# MuffsyRelayInput2.net
KiCad netlist of a schematic drawn in EAGLE
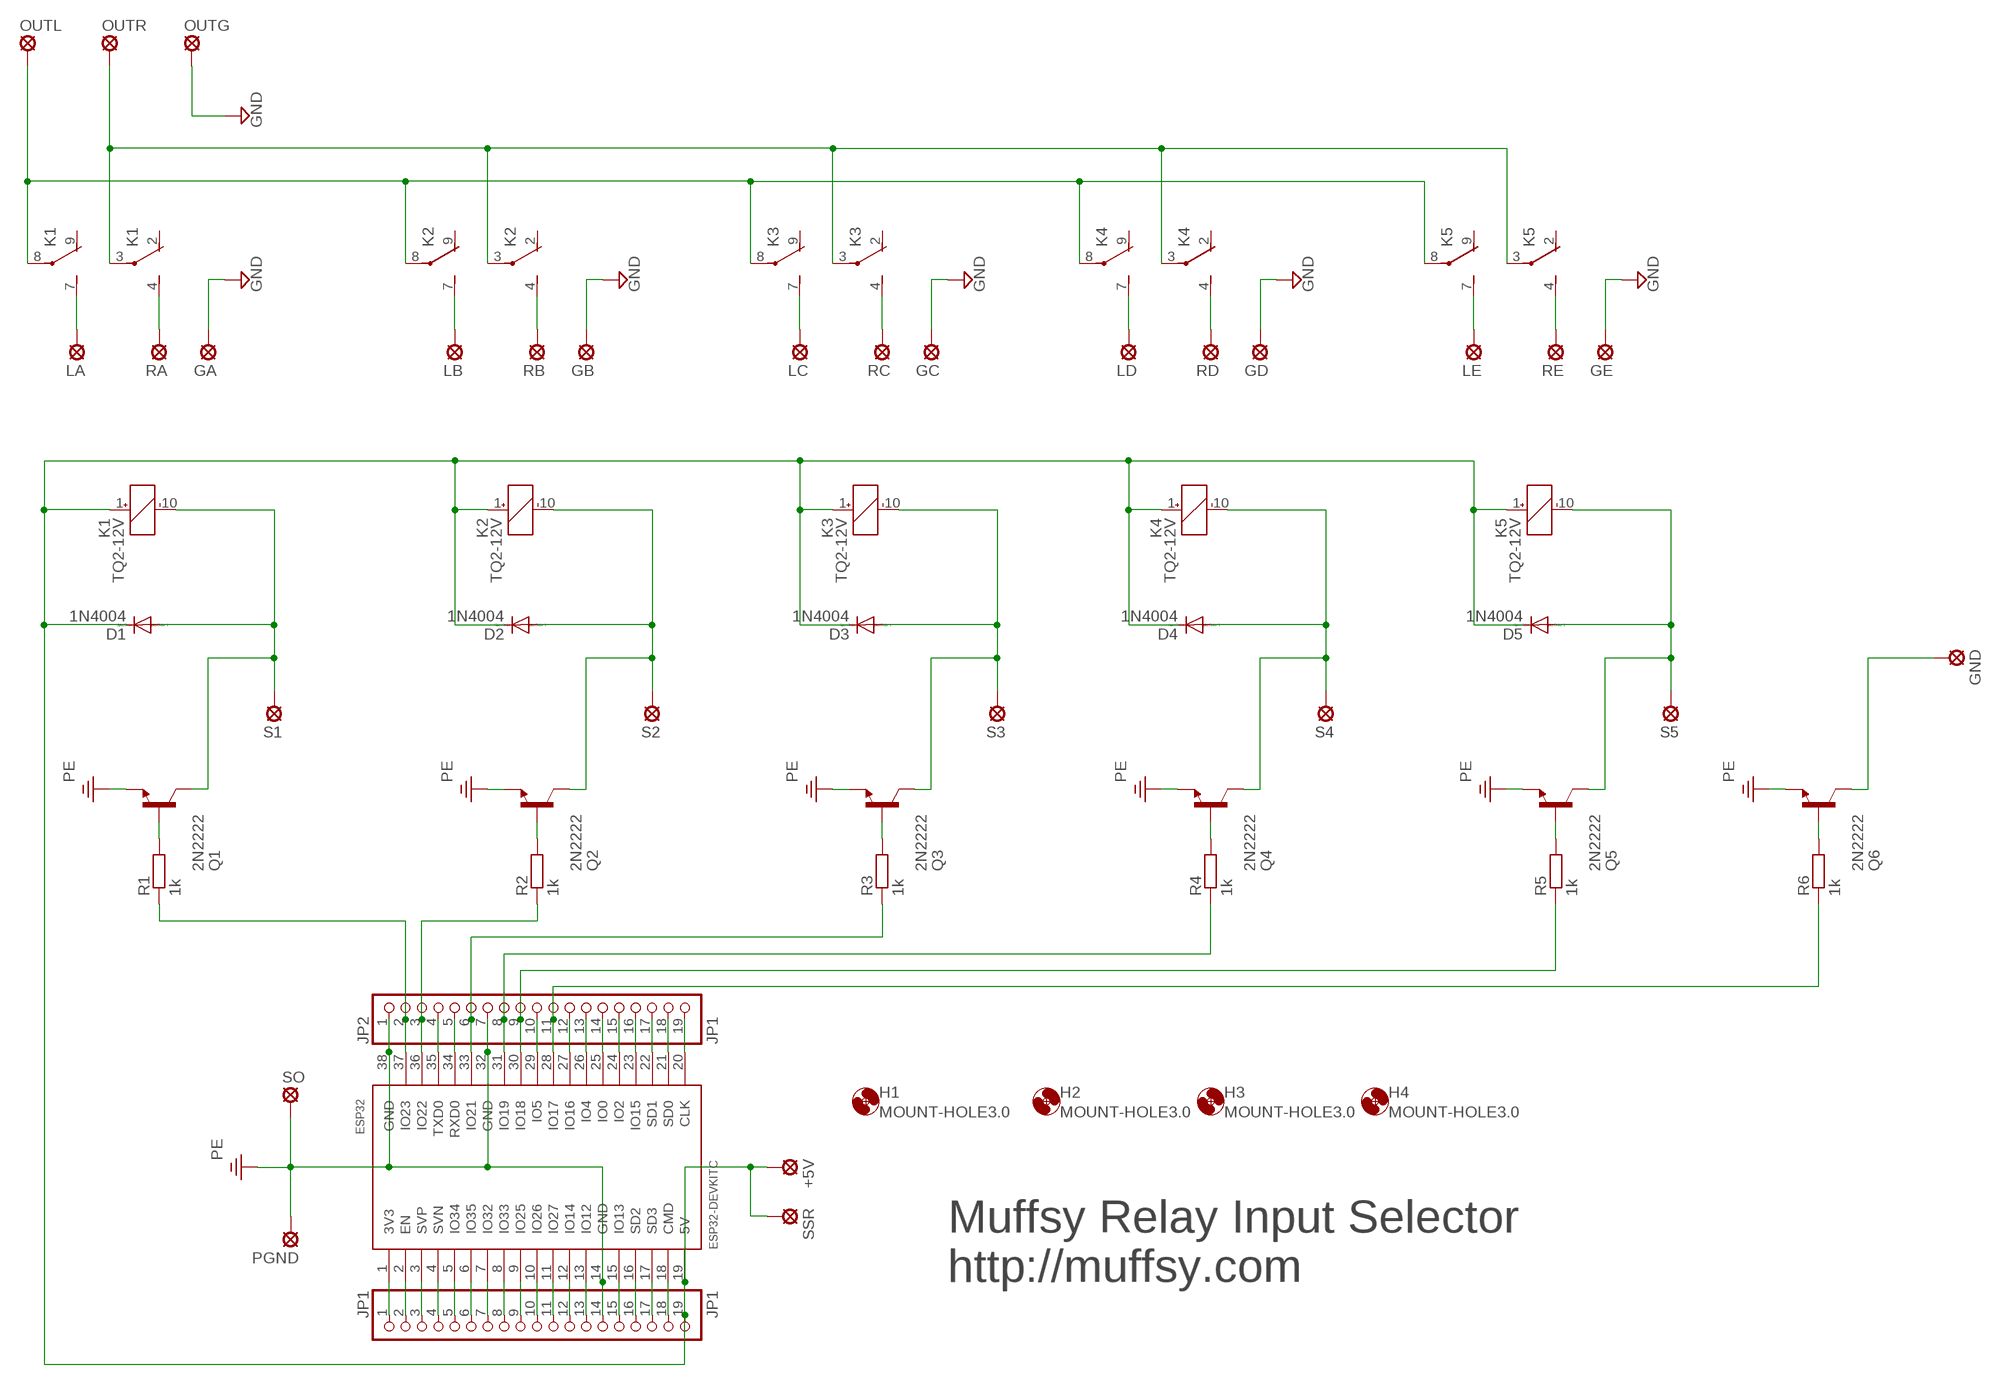
[diagram p0: schematic, sheet 1]

(export (version "E")
  (design (tool "Eeschema 10.0.6"))
  (components
    (comp (ref "+5V")
      (value "SE11")
      (footprint "eagle-import:SE11")
      (libsource (lib "eagle-import") (part "SE11"))
    )
    (comp (ref "D1")
      (value "1N4004")
      (footprint "eagle-import:DO41-10")
      (libsource (lib "eagle-import") (part "1N4004"))
    )
    (comp (ref "D2")
      (value "1N4004")
      (footprint "eagle-import:DO41-10")
      (libsource (lib "eagle-import") (part "1N4004"))
    )
    (comp (ref "D3")
      (value "1N4004")
      (footprint "eagle-import:DO41-10")
      (libsource (lib "eagle-import") (part "1N4004"))
    )
    (comp (ref "D4")
      (value "1N4004")
      (footprint "eagle-import:DO41-10")
      (libsource (lib "eagle-import") (part "1N4004"))
    )
    (comp (ref "D5")
      (value "1N4004")
      (footprint "eagle-import:DO41-10")
      (libsource (lib "eagle-import") (part "1N4004"))
    )
    (comp (ref "ESP32")
      (value "ESP32DEVKITC")
      (footprint "eagle-import:ESP32-DEVKITC")
      (libsource (lib "eagle-import") (part "ESP32DEVKITC"))
    )
    (comp (ref "GA")
      (value "SE11")
      (footprint "eagle-import:SE11")
      (libsource (lib "eagle-import") (part "SE11"))
    )
    (comp (ref "GB")
      (value "SE11")
      (footprint "eagle-import:SE11")
      (libsource (lib "eagle-import") (part "SE11"))
    )
    (comp (ref "GC")
      (value "SE11")
      (footprint "eagle-import:SE11")
      (libsource (lib "eagle-import") (part "SE11"))
    )
    (comp (ref "GD")
      (value "SE11")
      (footprint "eagle-import:SE11")
      (libsource (lib "eagle-import") (part "SE11"))
    )
    (comp (ref "GE")
      (value "SE11")
      (footprint "eagle-import:SE11")
      (libsource (lib "eagle-import") (part "SE11"))
    )
    (comp (ref "GND")
      (value "SE11")
      (footprint "eagle-import:SE11")
      (libsource (lib "eagle-import") (part "SE11"))
    )
    (comp (ref "H1")
      (value "MOUNT-HOLE3.0")
      (footprint "eagle-import:3,0")
      (libsource (lib "eagle-import") (part "MOUNT-HOLE3.0"))
    )
    (comp (ref "H2")
      (value "MOUNT-HOLE3.0")
      (footprint "eagle-import:3,0")
      (libsource (lib "eagle-import") (part "MOUNT-HOLE3.0"))
    )
    (comp (ref "H3")
      (value "MOUNT-HOLE3.0")
      (footprint "eagle-import:3,0")
      (libsource (lib "eagle-import") (part "MOUNT-HOLE3.0"))
    )
    (comp (ref "H4")
      (value "MOUNT-HOLE3.0")
      (footprint "eagle-import:3,0")
      (libsource (lib "eagle-import") (part "MOUNT-HOLE3.0"))
    )
    (comp (ref "JP1")
      (value "JP1")
      (footprint "eagle-import:1X19")
      (libsource (lib "eagle-import") (part "PINHD-1X19"))
    )
    (comp (ref "JP2")
      (value "JP1")
      (footprint "eagle-import:1X19")
      (libsource (lib "eagle-import") (part "PINHD-1X19"))
    )
    (comp (ref "K1")
      (value "TQ2-12V")
      (footprint "eagle-import:TQ2")
      (fields (field (name "MF") "AROMAT/ MATSUSHITA"))
      (libsource (lib "eagle-import") (part "TQ2?-12V"))
    )
    (comp (ref "K2")
      (value "TQ2-12V")
      (footprint "eagle-import:TQ2")
      (fields (field (name "MF") "AROMAT/ MATSUSHITA"))
      (libsource (lib "eagle-import") (part "TQ2?-12V"))
    )
    (comp (ref "K3")
      (value "TQ2-12V")
      (footprint "eagle-import:TQ2")
      (fields (field (name "MF") "AROMAT/ MATSUSHITA"))
      (libsource (lib "eagle-import") (part "TQ2?-12V"))
    )
    (comp (ref "K4")
      (value "TQ2-12V")
      (footprint "eagle-import:TQ2")
      (fields (field (name "MF") "AROMAT/ MATSUSHITA"))
      (libsource (lib "eagle-import") (part "TQ2?-12V"))
    )
    (comp (ref "K5")
      (value "TQ2-12V")
      (footprint "eagle-import:TQ2")
      (fields (field (name "MF") "AROMAT/ MATSUSHITA"))
      (libsource (lib "eagle-import") (part "TQ2?-12V"))
    )
    (comp (ref "LA")
      (value "SE11")
      (footprint "eagle-import:SE11")
      (libsource (lib "eagle-import") (part "SE11"))
    )
    (comp (ref "LB")
      (value "SE11")
      (footprint "eagle-import:SE11")
      (libsource (lib "eagle-import") (part "SE11"))
    )
    (comp (ref "LC")
      (value "SE11")
      (footprint "eagle-import:SE11")
      (libsource (lib "eagle-import") (part "SE11"))
    )
    (comp (ref "LD")
      (value "SE11")
      (footprint "eagle-import:SE11")
      (libsource (lib "eagle-import") (part "SE11"))
    )
    (comp (ref "LE")
      (value "SE11")
      (footprint "eagle-import:SE11")
      (libsource (lib "eagle-import") (part "SE11"))
    )
    (comp (ref "OUTG")
      (value "SE11")
      (footprint "eagle-import:SE11")
      (libsource (lib "eagle-import") (part "SE11"))
    )
    (comp (ref "OUTL")
      (value "SE11")
      (footprint "eagle-import:SE11")
      (libsource (lib "eagle-import") (part "SE11"))
    )
    (comp (ref "OUTR")
      (value "SE11")
      (footprint "eagle-import:SE11")
      (libsource (lib "eagle-import") (part "SE11"))
    )
    (comp (ref "PGND")
      (value "SE11")
      (footprint "eagle-import:SE11")
      (libsource (lib "eagle-import") (part "SE11"))
    )
    (comp (ref "Q1")
      (value "2N2222")
      (footprint "eagle-import:TO18")
      (libsource (lib "eagle-import") (part "2N2222"))
    )
    (comp (ref "Q2")
      (value "2N2222")
      (footprint "eagle-import:TO18")
      (libsource (lib "eagle-import") (part "2N2222"))
    )
    (comp (ref "Q3")
      (value "2N2222")
      (footprint "eagle-import:TO18")
      (libsource (lib "eagle-import") (part "2N2222"))
    )
    (comp (ref "Q4")
      (value "2N2222")
      (footprint "eagle-import:TO18")
      (libsource (lib "eagle-import") (part "2N2222"))
    )
    (comp (ref "Q5")
      (value "2N2222")
      (footprint "eagle-import:TO18")
      (libsource (lib "eagle-import") (part "2N2222"))
    )
    (comp (ref "Q6")
      (value "2N2222")
      (footprint "eagle-import:TO18")
      (libsource (lib "eagle-import") (part "2N2222"))
    )
    (comp (ref "R1")
      (value "1k")
      (footprint "eagle-import:0207_10")
      (libsource (lib "eagle-import") (part "R-EU_0207/10"))
    )
    (comp (ref "R2")
      (value "1k")
      (footprint "eagle-import:0207_10")
      (libsource (lib "eagle-import") (part "R-EU_0207/10"))
    )
    (comp (ref "R3")
      (value "1k")
      (footprint "eagle-import:0207_10")
      (libsource (lib "eagle-import") (part "R-EU_0207/10"))
    )
    (comp (ref "R4")
      (value "1k")
      (footprint "eagle-import:0207_10")
      (libsource (lib "eagle-import") (part "R-EU_0207/10"))
    )
    (comp (ref "R5")
      (value "1k")
      (footprint "eagle-import:0207_10")
      (libsource (lib "eagle-import") (part "R-EU_0207/10"))
    )
    (comp (ref "R6")
      (value "1k")
      (footprint "eagle-import:0207_10")
      (libsource (lib "eagle-import") (part "R-EU_0207/10"))
    )
    (comp (ref "RA")
      (value "SE11")
      (footprint "eagle-import:SE11")
      (libsource (lib "eagle-import") (part "SE11"))
    )
    (comp (ref "RB")
      (value "SE11")
      (footprint "eagle-import:SE11")
      (libsource (lib "eagle-import") (part "SE11"))
    )
    (comp (ref "RC")
      (value "SE11")
      (footprint "eagle-import:SE11")
      (libsource (lib "eagle-import") (part "SE11"))
    )
    (comp (ref "RD")
      (value "SE11")
      (footprint "eagle-import:SE11")
      (libsource (lib "eagle-import") (part "SE11"))
    )
    (comp (ref "RE")
      (value "SE11")
      (footprint "eagle-import:SE11")
      (libsource (lib "eagle-import") (part "SE11"))
    )
    (comp (ref "S1")
      (value "SE11")
      (footprint "eagle-import:SE11")
      (libsource (lib "eagle-import") (part "SE11"))
    )
    (comp (ref "S2")
      (value "SE11")
      (footprint "eagle-import:SE11")
      (libsource (lib "eagle-import") (part "SE11"))
    )
    (comp (ref "S3")
      (value "SE11")
      (footprint "eagle-import:SE11")
      (libsource (lib "eagle-import") (part "SE11"))
    )
    (comp (ref "S4")
      (value "SE11")
      (footprint "eagle-import:SE11")
      (libsource (lib "eagle-import") (part "SE11"))
    )
    (comp (ref "S5")
      (value "SE11")
      (footprint "eagle-import:SE11")
      (libsource (lib "eagle-import") (part "SE11"))
    )
    (comp (ref "SO")
      (value "SE11")
      (footprint "eagle-import:SE11")
      (libsource (lib "eagle-import") (part "SE11"))
    )
    (comp (ref "SSR")
      (value "SE11")
      (footprint "eagle-import:SE11")
      (libsource (lib "eagle-import") (part "SE11"))
    )
  )
  (nets
    (net (code "1") (name "GND") (class "Default")
      (node (ref "GA") (pin "MP") (pinfunction "MP_MP") (pintype "passive"))
      (node (ref "GB") (pin "MP") (pinfunction "MP_MP") (pintype "passive"))
      (node (ref "GC") (pin "MP") (pinfunction "MP_MP") (pintype "passive"))
      (node (ref "GD") (pin "MP") (pinfunction "MP_MP") (pintype "passive"))
      (node (ref "GE") (pin "MP") (pinfunction "MP_MP") (pintype "passive"))
      (node (ref "OUTG") (pin "MP") (pinfunction "MP_MP") (pintype "passive"))
    )
    (net (code "2") (name "Net-(ESP32-3V3)") (class "Default")
      (node (ref "ESP32") (pin "1") (pinfunction "3V3_1") (pintype "bidirectional"))
      (node (ref "JP1") (pin "1") (pinfunction "1_1") (pintype "passive"))
    )
    (net (code "3") (name "Net-(ESP32-5V)") (class "Default")
      (node (ref "+5V") (pin "MP") (pinfunction "MP_MP") (pintype "passive"))
      (node (ref "D1") (pin "C") (pinfunction "C_C") (pintype "passive"))
      (node (ref "D2") (pin "C") (pinfunction "C_C") (pintype "passive"))
      (node (ref "D3") (pin "C") (pinfunction "C_C") (pintype "passive"))
      (node (ref "D4") (pin "C") (pinfunction "C_C") (pintype "passive"))
      (node (ref "D5") (pin "C") (pinfunction "C_C") (pintype "passive"))
      (node (ref "ESP32") (pin "19") (pinfunction "5V_19") (pintype "bidirectional"))
      (node (ref "JP1") (pin "19") (pinfunction "19_19") (pintype "passive"))
      (node (ref "K1") (pin "1") (pinfunction "+_1") (pintype "passive"))
      (node (ref "K2") (pin "1") (pinfunction "+_1") (pintype "passive"))
      (node (ref "K3") (pin "1") (pinfunction "+_1") (pintype "passive"))
      (node (ref "K4") (pin "1") (pinfunction "+_1") (pintype "passive"))
      (node (ref "K5") (pin "1") (pinfunction "+_1") (pintype "passive"))
      (node (ref "SSR") (pin "MP") (pinfunction "MP_MP") (pintype "passive"))
    )
    (net (code "4") (name "Net-(ESP32-CLK)") (class "Default")
      (node (ref "ESP32") (pin "20") (pinfunction "CLK_20") (pintype "bidirectional"))
      (node (ref "JP2") (pin "19") (pinfunction "19_19") (pintype "passive"))
    )
    (net (code "5") (name "Net-(ESP32-CMD)") (class "Default")
      (node (ref "ESP32") (pin "18") (pinfunction "CMD_18") (pintype "bidirectional"))
      (node (ref "JP1") (pin "18") (pinfunction "18_18") (pintype "passive"))
    )
    (net (code "6") (name "Net-(ESP32-EN)") (class "Default")
      (node (ref "ESP32") (pin "2") (pinfunction "EN_2") (pintype "bidirectional"))
      (node (ref "JP1") (pin "2") (pinfunction "2_2") (pintype "passive"))
    )
    (net (code "7") (name "Net-(ESP32-IO0)") (class "Default")
      (node (ref "ESP32") (pin "25") (pinfunction "IO0_25") (pintype "bidirectional"))
      (node (ref "JP2") (pin "14") (pinfunction "14_14") (pintype "passive"))
    )
    (net (code "8") (name "Net-(ESP32-IO2)") (class "Default")
      (node (ref "ESP32") (pin "24") (pinfunction "IO2_24") (pintype "bidirectional"))
      (node (ref "JP2") (pin "15") (pinfunction "15_15") (pintype "passive"))
    )
    (net (code "9") (name "Net-(ESP32-IO4)") (class "Default")
      (node (ref "ESP32") (pin "26") (pinfunction "IO4_26") (pintype "bidirectional"))
      (node (ref "JP2") (pin "13") (pinfunction "13_13") (pintype "passive"))
    )
    (net (code "10") (name "Net-(ESP32-IO5)") (class "Default")
      (node (ref "ESP32") (pin "29") (pinfunction "IO5_29") (pintype "bidirectional"))
      (node (ref "JP2") (pin "10") (pinfunction "10_10") (pintype "passive"))
    )
    (net (code "11") (name "Net-(ESP32-IO12)") (class "Default")
      (node (ref "ESP32") (pin "13") (pinfunction "IO12_13") (pintype "bidirectional"))
      (node (ref "JP1") (pin "13") (pinfunction "13_13") (pintype "passive"))
    )
    (net (code "12") (name "Net-(ESP32-IO13)") (class "Default")
      (node (ref "ESP32") (pin "15") (pinfunction "IO13_15") (pintype "bidirectional"))
      (node (ref "JP1") (pin "15") (pinfunction "15_15") (pintype "passive"))
    )
    (net (code "13") (name "Net-(ESP32-IO14)") (class "Default")
      (node (ref "ESP32") (pin "12") (pinfunction "IO14_12") (pintype "bidirectional"))
      (node (ref "JP1") (pin "12") (pinfunction "12_12") (pintype "passive"))
    )
    (net (code "14") (name "Net-(ESP32-IO15)") (class "Default")
      (node (ref "ESP32") (pin "23") (pinfunction "IO15_23") (pintype "bidirectional"))
      (node (ref "JP2") (pin "16") (pinfunction "16_16") (pintype "passive"))
    )
    (net (code "15") (name "Net-(ESP32-IO16)") (class "Default")
      (node (ref "ESP32") (pin "27") (pinfunction "IO16_27") (pintype "bidirectional"))
      (node (ref "JP2") (pin "12") (pinfunction "12_12") (pintype "passive"))
    )
    (net (code "16") (name "Net-(ESP32-IO17)") (class "Default")
      (node (ref "ESP32") (pin "28") (pinfunction "IO17_28") (pintype "bidirectional"))
      (node (ref "JP2") (pin "11") (pinfunction "11_11") (pintype "passive"))
      (node (ref "R6") (pin "1") (pinfunction "1_1") (pintype "passive"))
    )
    (net (code "17") (name "Net-(ESP32-IO18)") (class "Default")
      (node (ref "ESP32") (pin "30") (pinfunction "IO18_30") (pintype "bidirectional"))
      (node (ref "JP2") (pin "9") (pinfunction "9_9") (pintype "passive"))
      (node (ref "R5") (pin "1") (pinfunction "1_1") (pintype "passive"))
    )
    (net (code "18") (name "Net-(ESP32-IO19)") (class "Default")
      (node (ref "ESP32") (pin "31") (pinfunction "IO19_31") (pintype "bidirectional"))
      (node (ref "JP2") (pin "8") (pinfunction "8_8") (pintype "passive"))
      (node (ref "R4") (pin "1") (pinfunction "1_1") (pintype "passive"))
    )
    (net (code "19") (name "Net-(ESP32-IO21)") (class "Default")
      (node (ref "ESP32") (pin "33") (pinfunction "IO21_33") (pintype "bidirectional"))
      (node (ref "JP2") (pin "6") (pinfunction "6_6") (pintype "passive"))
      (node (ref "R3") (pin "1") (pinfunction "1_1") (pintype "passive"))
    )
    (net (code "20") (name "Net-(ESP32-IO22)") (class "Default")
      (node (ref "ESP32") (pin "36") (pinfunction "IO22_36") (pintype "bidirectional"))
      (node (ref "JP2") (pin "3") (pinfunction "3_3") (pintype "passive"))
      (node (ref "R2") (pin "1") (pinfunction "1_1") (pintype "passive"))
    )
    (net (code "21") (name "Net-(ESP32-IO23)") (class "Default")
      (node (ref "ESP32") (pin "37") (pinfunction "IO23_37") (pintype "bidirectional"))
      (node (ref "JP2") (pin "2") (pinfunction "2_2") (pintype "passive"))
      (node (ref "R1") (pin "1") (pinfunction "1_1") (pintype "passive"))
    )
    (net (code "22") (name "Net-(ESP32-IO25)") (class "Default")
      (node (ref "ESP32") (pin "9") (pinfunction "IO25_9") (pintype "bidirectional"))
      (node (ref "JP1") (pin "9") (pinfunction "9_9") (pintype "passive"))
    )
    (net (code "23") (name "Net-(ESP32-IO26)") (class "Default")
      (node (ref "ESP32") (pin "10") (pinfunction "IO26_10") (pintype "bidirectional"))
      (node (ref "JP1") (pin "10") (pinfunction "10_10") (pintype "passive"))
    )
    (net (code "24") (name "Net-(ESP32-IO27)") (class "Default")
      (node (ref "ESP32") (pin "11") (pinfunction "IO27_11") (pintype "bidirectional"))
      (node (ref "JP1") (pin "11") (pinfunction "11_11") (pintype "passive"))
    )
    (net (code "25") (name "Net-(ESP32-IO32)") (class "Default")
      (node (ref "ESP32") (pin "7") (pinfunction "IO32_7") (pintype "bidirectional"))
      (node (ref "JP1") (pin "7") (pinfunction "7_7") (pintype "passive"))
    )
    (net (code "26") (name "Net-(ESP32-IO33)") (class "Default")
      (node (ref "ESP32") (pin "8") (pinfunction "IO33_8") (pintype "bidirectional"))
      (node (ref "JP1") (pin "8") (pinfunction "8_8") (pintype "passive"))
    )
    (net (code "27") (name "Net-(ESP32-IO34)") (class "Default")
      (node (ref "ESP32") (pin "5") (pinfunction "IO34_5") (pintype "bidirectional"))
      (node (ref "JP1") (pin "5") (pinfunction "5_5") (pintype "passive"))
    )
    (net (code "28") (name "Net-(ESP32-IO35)") (class "Default")
      (node (ref "ESP32") (pin "6") (pinfunction "IO35_6") (pintype "bidirectional"))
      (node (ref "JP1") (pin "6") (pinfunction "6_6") (pintype "passive"))
    )
    (net (code "29") (name "Net-(ESP32-RXD0)") (class "Default")
      (node (ref "ESP32") (pin "34") (pinfunction "RXD0_34") (pintype "bidirectional"))
      (node (ref "JP2") (pin "5") (pinfunction "5_5") (pintype "passive"))
    )
    (net (code "30") (name "Net-(ESP32-SD0)") (class "Default")
      (node (ref "ESP32") (pin "21") (pinfunction "SD0_21") (pintype "bidirectional"))
      (node (ref "JP2") (pin "18") (pinfunction "18_18") (pintype "passive"))
    )
    (net (code "31") (name "Net-(ESP32-SD1)") (class "Default")
      (node (ref "ESP32") (pin "22") (pinfunction "SD1_22") (pintype "bidirectional"))
      (node (ref "JP2") (pin "17") (pinfunction "17_17") (pintype "passive"))
    )
    (net (code "32") (name "Net-(ESP32-SD2)") (class "Default")
      (node (ref "ESP32") (pin "16") (pinfunction "SD2_16") (pintype "bidirectional"))
      (node (ref "JP1") (pin "16") (pinfunction "16_16") (pintype "passive"))
    )
    (net (code "33") (name "Net-(ESP32-SD3)") (class "Default")
      (node (ref "ESP32") (pin "17") (pinfunction "SD3_17") (pintype "bidirectional"))
      (node (ref "JP1") (pin "17") (pinfunction "17_17") (pintype "passive"))
    )
    (net (code "34") (name "Net-(ESP32-SVN)") (class "Default")
      (node (ref "ESP32") (pin "4") (pinfunction "SVN_4") (pintype "bidirectional"))
      (node (ref "JP1") (pin "4") (pinfunction "4_4") (pintype "passive"))
    )
    (net (code "35") (name "Net-(ESP32-SVP)") (class "Default")
      (node (ref "ESP32") (pin "3") (pinfunction "SVP_3") (pintype "bidirectional"))
      (node (ref "JP1") (pin "3") (pinfunction "3_3") (pintype "passive"))
    )
    (net (code "36") (name "Net-(ESP32-TXD0)") (class "Default")
      (node (ref "ESP32") (pin "35") (pinfunction "TXD0_35") (pintype "bidirectional"))
      (node (ref "JP2") (pin "4") (pinfunction "4_4") (pintype "passive"))
    )
    (net (code "37") (name "Net-(K1A-P)") (class "Default")
      (node (ref "K1") (pin "3") (pinfunction "P_3") (pintype "passive"))
      (node (ref "K2") (pin "3") (pinfunction "P_3") (pintype "passive"))
      (node (ref "K3") (pin "3") (pinfunction "P_3") (pintype "passive"))
      (node (ref "K4") (pin "3") (pinfunction "P_3") (pintype "passive"))
      (node (ref "K5") (pin "3") (pinfunction "P_3") (pintype "passive"))
      (node (ref "OUTR") (pin "MP") (pinfunction "MP_MP") (pintype "passive"))
    )
    (net (code "38") (name "Net-(K1A-S)") (class "Default")
      (node (ref "K1") (pin "4") (pinfunction "S_4") (pintype "passive"))
      (node (ref "RA") (pin "MP") (pinfunction "MP_MP") (pintype "passive"))
    )
    (net (code "39") (name "Net-(K1B-P)") (class "Default")
      (node (ref "K1") (pin "8") (pinfunction "P_8") (pintype "passive"))
      (node (ref "K2") (pin "8") (pinfunction "P_8") (pintype "passive"))
      (node (ref "K3") (pin "8") (pinfunction "P_8") (pintype "passive"))
      (node (ref "K4") (pin "8") (pinfunction "P_8") (pintype "passive"))
      (node (ref "K5") (pin "8") (pinfunction "P_8") (pintype "passive"))
      (node (ref "OUTL") (pin "MP") (pinfunction "MP_MP") (pintype "passive"))
    )
    (net (code "40") (name "Net-(K1B-S)") (class "Default")
      (node (ref "K1") (pin "7") (pinfunction "S_7") (pintype "passive"))
      (node (ref "LA") (pin "MP") (pinfunction "MP_MP") (pintype "passive"))
    )
    (net (code "41") (name "Net-(K1C--)") (class "Default")
      (node (ref "D1") (pin "A") (pinfunction "A_A") (pintype "passive"))
      (node (ref "K1") (pin "10") (pinfunction "-_10") (pintype "passive"))
      (node (ref "Q1") (pin "3") (pinfunction "C_3") (pintype "passive"))
      (node (ref "S1") (pin "MP") (pinfunction "MP_MP") (pintype "passive"))
    )
    (net (code "42") (name "Net-(K2A-S)") (class "Default")
      (node (ref "K2") (pin "4") (pinfunction "S_4") (pintype "passive"))
      (node (ref "RB") (pin "MP") (pinfunction "MP_MP") (pintype "passive"))
    )
    (net (code "43") (name "Net-(K2B-S)") (class "Default")
      (node (ref "K2") (pin "7") (pinfunction "S_7") (pintype "passive"))
      (node (ref "LB") (pin "MP") (pinfunction "MP_MP") (pintype "passive"))
    )
    (net (code "44") (name "Net-(K2C--)") (class "Default")
      (node (ref "D2") (pin "A") (pinfunction "A_A") (pintype "passive"))
      (node (ref "K2") (pin "10") (pinfunction "-_10") (pintype "passive"))
      (node (ref "Q2") (pin "3") (pinfunction "C_3") (pintype "passive"))
      (node (ref "S2") (pin "MP") (pinfunction "MP_MP") (pintype "passive"))
    )
    (net (code "45") (name "Net-(K3A-S)") (class "Default")
      (node (ref "K3") (pin "4") (pinfunction "S_4") (pintype "passive"))
      (node (ref "RC") (pin "MP") (pinfunction "MP_MP") (pintype "passive"))
    )
    (net (code "46") (name "Net-(K3B-S)") (class "Default")
      (node (ref "K3") (pin "7") (pinfunction "S_7") (pintype "passive"))
      (node (ref "LC") (pin "MP") (pinfunction "MP_MP") (pintype "passive"))
    )
    (net (code "47") (name "Net-(K3C--)") (class "Default")
      (node (ref "D3") (pin "A") (pinfunction "A_A") (pintype "passive"))
      (node (ref "K3") (pin "10") (pinfunction "-_10") (pintype "passive"))
      (node (ref "Q3") (pin "3") (pinfunction "C_3") (pintype "passive"))
      (node (ref "S3") (pin "MP") (pinfunction "MP_MP") (pintype "passive"))
    )
    (net (code "48") (name "Net-(K4A-S)") (class "Default")
      (node (ref "K4") (pin "4") (pinfunction "S_4") (pintype "passive"))
      (node (ref "RD") (pin "MP") (pinfunction "MP_MP") (pintype "passive"))
    )
    (net (code "49") (name "Net-(K4B-S)") (class "Default")
      (node (ref "K4") (pin "7") (pinfunction "S_7") (pintype "passive"))
      (node (ref "LD") (pin "MP") (pinfunction "MP_MP") (pintype "passive"))
    )
    (net (code "50") (name "Net-(K4C--)") (class "Default")
      (node (ref "D4") (pin "A") (pinfunction "A_A") (pintype "passive"))
      (node (ref "K4") (pin "10") (pinfunction "-_10") (pintype "passive"))
      (node (ref "Q4") (pin "3") (pinfunction "C_3") (pintype "passive"))
      (node (ref "S4") (pin "MP") (pinfunction "MP_MP") (pintype "passive"))
    )
    (net (code "51") (name "Net-(K5A-S)") (class "Default")
      (node (ref "K5") (pin "4") (pinfunction "S_4") (pintype "passive"))
      (node (ref "RE") (pin "MP") (pinfunction "MP_MP") (pintype "passive"))
    )
    (net (code "52") (name "Net-(K5B-S)") (class "Default")
      (node (ref "K5") (pin "7") (pinfunction "S_7") (pintype "passive"))
      (node (ref "LE") (pin "MP") (pinfunction "MP_MP") (pintype "passive"))
    )
    (net (code "53") (name "Net-(K5C--)") (class "Default")
      (node (ref "D5") (pin "A") (pinfunction "A_A") (pintype "passive"))
      (node (ref "K5") (pin "10") (pinfunction "-_10") (pintype "passive"))
      (node (ref "Q5") (pin "3") (pinfunction "C_3") (pintype "passive"))
      (node (ref "S5") (pin "MP") (pinfunction "MP_MP") (pintype "passive"))
    )
    (net (code "54") (name "Net-(Q1-B)") (class "Default")
      (node (ref "Q1") (pin "2") (pinfunction "B_2") (pintype "passive"))
      (node (ref "R1") (pin "2") (pinfunction "2_2") (pintype "passive"))
    )
    (net (code "55") (name "Net-(Q2-B)") (class "Default")
      (node (ref "Q2") (pin "2") (pinfunction "B_2") (pintype "passive"))
      (node (ref "R2") (pin "2") (pinfunction "2_2") (pintype "passive"))
    )
    (net (code "56") (name "Net-(Q3-B)") (class "Default")
      (node (ref "Q3") (pin "2") (pinfunction "B_2") (pintype "passive"))
      (node (ref "R3") (pin "2") (pinfunction "2_2") (pintype "passive"))
    )
    (net (code "57") (name "Net-(Q4-B)") (class "Default")
      (node (ref "Q4") (pin "2") (pinfunction "B_2") (pintype "passive"))
      (node (ref "R4") (pin "2") (pinfunction "2_2") (pintype "passive"))
    )
    (net (code "58") (name "Net-(Q5-B)") (class "Default")
      (node (ref "Q5") (pin "2") (pinfunction "B_2") (pintype "passive"))
      (node (ref "R5") (pin "2") (pinfunction "2_2") (pintype "passive"))
    )
    (net (code "59") (name "Net-(Q6-B)") (class "Default")
      (node (ref "Q6") (pin "2") (pinfunction "B_2") (pintype "passive"))
      (node (ref "R6") (pin "2") (pinfunction "2_2") (pintype "passive"))
    )
    (net (code "60") (name "Net-(Q6-C)") (class "Default")
      (node (ref "GND") (pin "MP") (pinfunction "MP_MP") (pintype "passive"))
      (node (ref "Q6") (pin "3") (pinfunction "C_3") (pintype "passive"))
    )
    (net (code "61") (name "PE") (class "Default")
      (node (ref "ESP32") (pin "14") (pinfunction "GND_14") (pintype "bidirectional"))
      (node (ref "ESP32") (pin "32") (pinfunction "GND_32") (pintype "bidirectional"))
      (node (ref "ESP32") (pin "38") (pinfunction "GND_38") (pintype "bidirectional"))
      (node (ref "JP1") (pin "14") (pinfunction "14_14") (pintype "passive"))
      (node (ref "JP2") (pin "1") (pinfunction "1_1") (pintype "passive"))
      (node (ref "JP2") (pin "7") (pinfunction "7_7") (pintype "passive"))
      (node (ref "PGND") (pin "MP") (pinfunction "MP_MP") (pintype "passive"))
      (node (ref "Q1") (pin "1") (pinfunction "E_1") (pintype "passive"))
      (node (ref "Q2") (pin "1") (pinfunction "E_1") (pintype "passive"))
      (node (ref "Q3") (pin "1") (pinfunction "E_1") (pintype "passive"))
      (node (ref "Q4") (pin "1") (pinfunction "E_1") (pintype "passive"))
      (node (ref "Q5") (pin "1") (pinfunction "E_1") (pintype "passive"))
      (node (ref "Q6") (pin "1") (pinfunction "E_1") (pintype "passive"))
      (node (ref "SO") (pin "MP") (pinfunction "MP_MP") (pintype "passive"))
    )
    (net (code "62") (name "unconnected-(K1A-O-Pad2)") (class "Default")
      (node (ref "K1") (pin "2") (pinfunction "O_2") (pintype "passive"))
    )
    (net (code "63") (name "unconnected-(K1B-O-Pad9)") (class "Default")
      (node (ref "K1") (pin "9") (pinfunction "O_9") (pintype "passive"))
    )
    (net (code "64") (name "unconnected-(K2A-O-Pad2)") (class "Default")
      (node (ref "K2") (pin "2") (pinfunction "O_2") (pintype "passive"))
    )
    (net (code "65") (name "unconnected-(K2B-O-Pad9)") (class "Default")
      (node (ref "K2") (pin "9") (pinfunction "O_9") (pintype "passive"))
    )
    (net (code "66") (name "unconnected-(K3A-O-Pad2)") (class "Default")
      (node (ref "K3") (pin "2") (pinfunction "O_2") (pintype "passive"))
    )
    (net (code "67") (name "unconnected-(K3B-O-Pad9)") (class "Default")
      (node (ref "K3") (pin "9") (pinfunction "O_9") (pintype "passive"))
    )
    (net (code "68") (name "unconnected-(K4A-O-Pad2)") (class "Default")
      (node (ref "K4") (pin "2") (pinfunction "O_2") (pintype "passive"))
    )
    (net (code "69") (name "unconnected-(K4B-O-Pad9)") (class "Default")
      (node (ref "K4") (pin "9") (pinfunction "O_9") (pintype "passive"))
    )
    (net (code "70") (name "unconnected-(K5A-O-Pad2)") (class "Default")
      (node (ref "K5") (pin "2") (pinfunction "O_2") (pintype "passive"))
    )
    (net (code "71") (name "unconnected-(K5B-O-Pad9)") (class "Default")
      (node (ref "K5") (pin "9") (pinfunction "O_9") (pintype "passive"))
    )
  )
)
